# CurrentSenseAmplfier_DifferentialInstrum.net
KiCad netlist of a schematic drawn in EasyEDA Pro
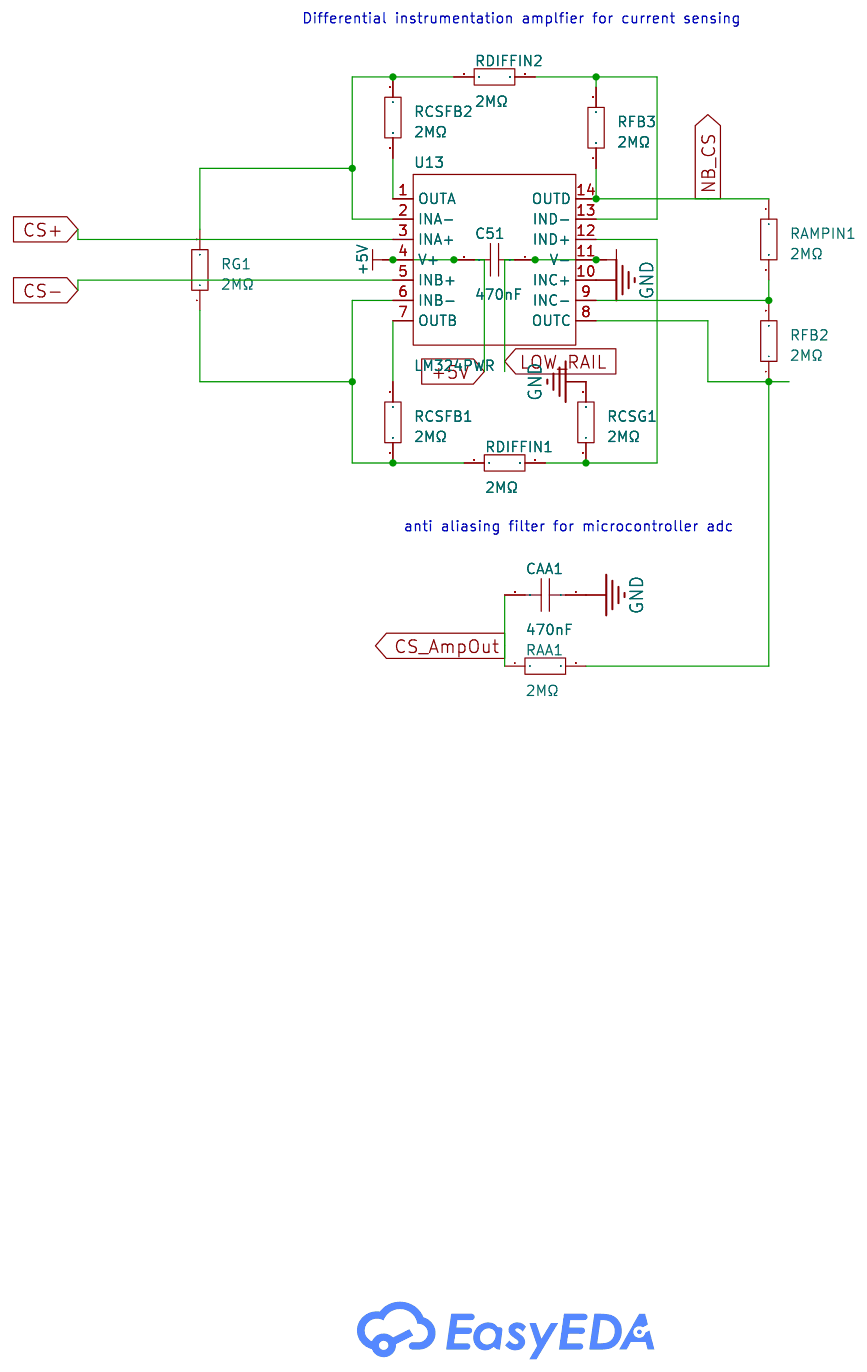
[diagram p0: schematic sheet]

(export (version "E")
  (design (tool "Eeschema 10.0.6"))
  (components
    (comp (ref "C51")
      (value "470nF")
      (footprint "easyedapro:CAP-TH_L7.2-W2.5-P5.00-D0.5")
      (fields
        (field (name "Manufacturer Part") "C241J474J20C000")
        (field (name "Manufacturer") "faratronic(厦门法拉)")
      )
      (libsource (lib "easyedapro") (part "C241J474J20C000"))
    )
    (comp (ref "CAA1")
      (value "470nF")
      (footprint "easyedapro:CAP-TH_L7.2-W2.5-P5.00-D0.5")
      (fields
        (field (name "Manufacturer Part") "C241J474J20C000")
        (field (name "Manufacturer") "faratronic(厦门法拉)")
      )
      (libsource (lib "easyedapro") (part "C241J474J20C000"))
    )
    (comp (ref "RAA1")
      (value "2MΩ")
      (fields (field (name "Manufacturer Part") "SCR0805J2M") (field (name "Manufacturer") "VO(翔胜)"))
      (libsource (lib "easyedapro") (part "Res"))
    )
    (comp (ref "RAMPIN1")
      (value "2MΩ")
      (fields (field (name "Manufacturer Part") "SCR0805J2M") (field (name "Manufacturer") "VO(翔胜)"))
      (libsource (lib "easyedapro") (part "Res"))
    )
    (comp (ref "RCSFB1")
      (value "2MΩ")
      (fields (field (name "Manufacturer Part") "SCR0805J2M") (field (name "Manufacturer") "VO(翔胜)"))
      (libsource (lib "easyedapro") (part "Res"))
    )
    (comp (ref "RCSFB2")
      (value "2MΩ")
      (fields (field (name "Manufacturer Part") "SCR0805J2M") (field (name "Manufacturer") "VO(翔胜)"))
      (libsource (lib "easyedapro") (part "Res"))
    )
    (comp (ref "RCSG1")
      (value "2MΩ")
      (fields (field (name "Manufacturer Part") "SCR0805J2M") (field (name "Manufacturer") "VO(翔胜)"))
      (libsource (lib "easyedapro") (part "Res"))
    )
    (comp (ref "RDIFFIN1")
      (value "2MΩ")
      (fields (field (name "Manufacturer Part") "SCR0805J2M") (field (name "Manufacturer") "VO(翔胜)"))
      (libsource (lib "easyedapro") (part "Res"))
    )
    (comp (ref "RDIFFIN2")
      (value "2MΩ")
      (fields (field (name "Manufacturer Part") "SCR0805J2M") (field (name "Manufacturer") "VO(翔胜)"))
      (libsource (lib "easyedapro") (part "Res"))
    )
    (comp (ref "RFB2")
      (value "2MΩ")
      (fields (field (name "Manufacturer Part") "SCR0805J2M") (field (name "Manufacturer") "VO(翔胜)"))
      (libsource (lib "easyedapro") (part "Res"))
    )
    (comp (ref "RFB3")
      (value "2MΩ")
      (fields (field (name "Manufacturer Part") "SCR0805J2M") (field (name "Manufacturer") "VO(翔胜)"))
      (libsource (lib "easyedapro") (part "Res"))
    )
    (comp (ref "RG1")
      (value "2MΩ")
      (fields (field (name "Manufacturer Part") "SCR0805J2M") (field (name "Manufacturer") "VO(翔胜)"))
      (libsource (lib "easyedapro") (part "Res"))
    )
    (comp (ref "U13")
      (value "LM324PWR")
      (footprint "easyedapro:TSSOP-14_L5.0-W4.4-P0.65-LS6.4-BL")
      (fields (field (name "Manufacturer") "TI(德州仪器)"))
      (libsource (lib "easyedapro") (part "LM324PWR"))
    )
  )
  (nets
    (net (code "1") (name "+5V") (class "Default")
      (node (ref "C51") (pin "2") (pinfunction "2_2") (pintype "unspecified"))
      (node (ref "U13") (pin "4") (pinfunction "V+_4") (pintype "unspecified"))
    )
    (net (code "2") (name "CS+") (class "Default")
      (node (ref "U13") (pin "3") (pinfunction "INA+_3") (pintype "unspecified"))
    )
    (net (code "3") (name "CS-") (class "Default")
      (node (ref "U13") (pin "5") (pinfunction "INB+_5") (pintype "unspecified"))
    )
    (net (code "4") (name "CS_AmpOut") (class "Default")
      (node (ref "CAA1") (pin "2") (pinfunction "2_2") (pintype "unspecified"))
      (node (ref "RAA1") (pin "1") (pinfunction "1_1") (pintype "input"))
    )
    (net (code "5") (name "GND") (class "Default")
      (node (ref "CAA1") (pin "1") (pinfunction "1_1") (pintype "unspecified"))
      (node (ref "RCSG1") (pin "2") (pinfunction "2_2") (pintype "input"))
      (node (ref "U13") (pin "10") (pinfunction "INC+_10") (pintype "unspecified"))
    )
    (net (code "6") (name "LOW_RAIL") (class "Default")
      (node (ref "C51") (pin "1") (pinfunction "1_1") (pintype "unspecified"))
      (node (ref "U13") (pin "11") (pinfunction "V-_11") (pintype "unspecified"))
    )
    (net (code "7") (name "NB_CS") (class "Default")
      (node (ref "RAMPIN1") (pin "1") (pinfunction "1_1") (pintype "input"))
      (node (ref "RFB3") (pin "1") (pinfunction "1_1") (pintype "input"))
      (node (ref "U13") (pin "14") (pinfunction "OUTD_14") (pintype "unspecified"))
    )
    (net (code "8") (name "Net-(U13-INA-)") (class "Default")
      (node (ref "RCSFB2") (pin "1") (pinfunction "1_1") (pintype "input"))
      (node (ref "RDIFFIN2") (pin "1") (pinfunction "1_1") (pintype "input"))
      (node (ref "RG1") (pin "2") (pinfunction "2_2") (pintype "input"))
      (node (ref "U13") (pin "2") (pinfunction "INA-_2") (pintype "unspecified"))
    )
    (net (code "9") (name "Net-(U13-INB-)") (class "Default")
      (node (ref "RCSFB1") (pin "2") (pinfunction "2_2") (pintype "input"))
      (node (ref "RDIFFIN1") (pin "1") (pinfunction "1_1") (pintype "input"))
      (node (ref "RG1") (pin "1") (pinfunction "1_1") (pintype "input"))
      (node (ref "U13") (pin "6") (pinfunction "INB-_6") (pintype "unspecified"))
    )
    (net (code "10") (name "Net-(U13-INC-)") (class "Default")
      (node (ref "RAMPIN1") (pin "2") (pinfunction "2_2") (pintype "input"))
      (node (ref "RFB2") (pin "2") (pinfunction "2_2") (pintype "input"))
      (node (ref "U13") (pin "9") (pinfunction "INC-_9") (pintype "unspecified"))
    )
    (net (code "11") (name "Net-(U13-IND+)") (class "Default")
      (node (ref "RCSG1") (pin "1") (pinfunction "1_1") (pintype "input"))
      (node (ref "RDIFFIN1") (pin "2") (pinfunction "2_2") (pintype "input"))
      (node (ref "U13") (pin "12") (pinfunction "IND+_12") (pintype "unspecified"))
    )
    (net (code "12") (name "Net-(U13-IND-)") (class "Default")
      (node (ref "RDIFFIN2") (pin "2") (pinfunction "2_2") (pintype "input"))
      (node (ref "RFB3") (pin "2") (pinfunction "2_2") (pintype "input"))
      (node (ref "U13") (pin "13") (pinfunction "IND-_13") (pintype "unspecified"))
    )
    (net (code "13") (name "Net-(U13-OUTA)") (class "Default")
      (node (ref "RCSFB2") (pin "2") (pinfunction "2_2") (pintype "input"))
      (node (ref "U13") (pin "1") (pinfunction "OUTA_1") (pintype "unspecified"))
    )
    (net (code "14") (name "Net-(U13-OUTB)") (class "Default")
      (node (ref "RCSFB1") (pin "1") (pinfunction "1_1") (pintype "input"))
      (node (ref "U13") (pin "7") (pinfunction "OUTB_7") (pintype "unspecified"))
    )
    (net (code "15") (name "Net-(U13-OUTC)") (class "Default")
      (node (ref "RAA1") (pin "2") (pinfunction "2_2") (pintype "input"))
      (node (ref "RFB2") (pin "1") (pinfunction "1_1") (pintype "input"))
      (node (ref "U13") (pin "8") (pinfunction "OUTC_8") (pintype "unspecified"))
    )
  )
)
